# PowerSupp.net
KiCad netlist of a schematic drawn in EAGLE
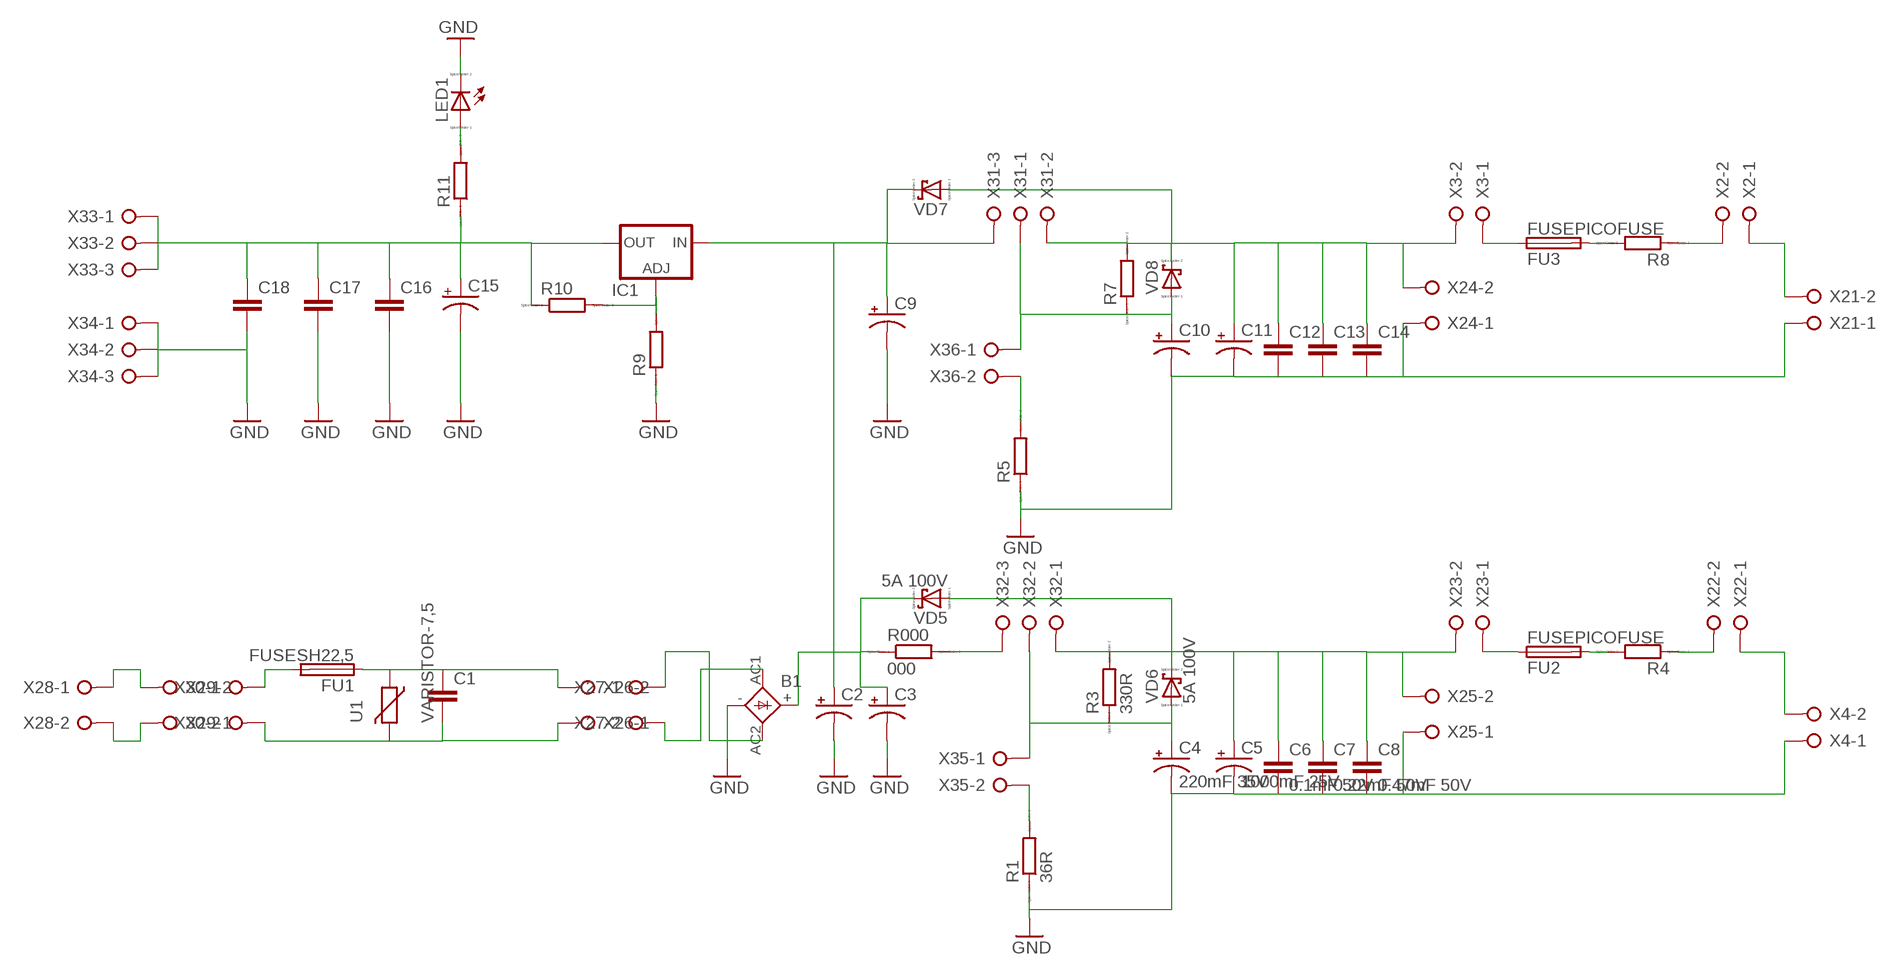
[diagram p0: schematic, sheet 1]

(export (version "E")
  (design (tool "Eeschema 10.0.6"))
  (components
    (comp (ref "B1")
      (value "KBU")
      (footprint "eagle-import:KBU")
      (libsource (lib "eagle-import") (part "KBU"))
    )
    (comp (ref "C1")
      (value "C15/8")
      (footprint "eagle-import:C15B8")
      (libsource (lib "eagle-import") (part "C15/8"))
    )
    (comp (ref "C2")
      (value "CPOL-USE7.5-16")
      (footprint "eagle-import:E7,5-16")
      (libsource (lib "eagle-import") (part "CPOL-USE7.5-16"))
    )
    (comp (ref "C3")
      (value "CPOL-USE7.5-16")
      (footprint "eagle-import:E7,5-16")
      (libsource (lib "eagle-import") (part "CPOL-USE7.5-16"))
    )
    (comp (ref "C4")
      (value "220mF 35V")
      (footprint "eagle-import:E5-10,5")
      (libsource (lib "eagle-import") (part "CPOL-USE5-10.5"))
    )
    (comp (ref "C5")
      (value "1000mF 25V")
      (footprint "eagle-import:E5-13")
      (libsource (lib "eagle-import") (part "CPOL-USE5-13"))
    )
    (comp (ref "C6")
      (value "0.1mF 50V")
      (footprint "eagle-import:C050-045X075")
      (libsource (lib "eagle-import") (part "C-EU050-045X075"))
    )
    (comp (ref "C7")
      (value "0.22mF 50V")
      (footprint "eagle-import:C050-045X075")
      (libsource (lib "eagle-import") (part "C-EU050-045X075"))
    )
    (comp (ref "C8")
      (value "0.47mF 50V")
      (footprint "eagle-import:C050-045X075")
      (libsource (lib "eagle-import") (part "C-EU050-045X075"))
    )
    (comp (ref "C9")
      (value "CPOL-USE7.5-16")
      (footprint "eagle-import:E7,5-16")
      (libsource (lib "eagle-import") (part "CPOL-USE7.5-16"))
    )
    (comp (ref "C10")
      (value "CPOL-USE5-10.5")
      (footprint "eagle-import:E5-10,5")
      (libsource (lib "eagle-import") (part "CPOL-USE5-10.5"))
    )
    (comp (ref "C11")
      (value "CPOL-USE5-13")
      (footprint "eagle-import:E5-13")
      (libsource (lib "eagle-import") (part "CPOL-USE5-13"))
    )
    (comp (ref "C12")
      (value "C-EU050-045X075")
      (footprint "eagle-import:C050-045X075")
      (libsource (lib "eagle-import") (part "C-EU050-045X075"))
    )
    (comp (ref "C13")
      (value "C-EU050-045X075")
      (footprint "eagle-import:C050-045X075")
      (libsource (lib "eagle-import") (part "C-EU050-045X075"))
    )
    (comp (ref "C14")
      (value "C-EU050-045X075")
      (footprint "eagle-import:C050-045X075")
      (libsource (lib "eagle-import") (part "C-EU050-045X075"))
    )
    (comp (ref "C15")
      (value "CPOL-USE5-10.5")
      (footprint "eagle-import:E5-10,5")
      (libsource (lib "eagle-import") (part "CPOL-USE5-10.5"))
    )
    (comp (ref "C16")
      (value "C-EU050-045X075")
      (footprint "eagle-import:C050-045X075")
      (libsource (lib "eagle-import") (part "C-EU050-045X075"))
    )
    (comp (ref "C17")
      (value "C-EU050-045X075")
      (footprint "eagle-import:C050-045X075")
      (libsource (lib "eagle-import") (part "C-EU050-045X075"))
    )
    (comp (ref "C18")
      (value "C-EU050-045X075")
      (footprint "eagle-import:C050-045X075")
      (libsource (lib "eagle-import") (part "C-EU050-045X075"))
    )
    (comp (ref "FU1")
      (value "FUSESH22,5")
      (footprint "eagle-import:SH22,5")
      (libsource (lib "eagle-import") (part "FUSESH22,5"))
    )
    (comp (ref "FU2")
      (value "FUSEPICOFUSE")
      (footprint "eagle-import:PICOFUSE")
      (libsource (lib "eagle-import") (part "FUSEPICOFUSE"))
    )
    (comp (ref "FU3")
      (value "FUSEPICOFUSE")
      (footprint "eagle-import:PICOFUSE")
      (libsource (lib "eagle-import") (part "FUSEPICOFUSE"))
    )
    (comp (ref "IC1")
      (value "LM317TL")
      (footprint "eagle-import:317TL")
      (libsource (lib "eagle-import") (part "LM317TL"))
    )
    (comp (ref "LED1")
      (value "LED_ELD260")
      (footprint "eagle-import:LED_LD260")
      (libsource (lib "eagle-import") (part "LED_ELD260"))
    )
    (comp (ref "R000")
      (value "000")
      (footprint "eagle-import:0207_10")
      (libsource (lib "eagle-import") (part "R0207/10"))
    )
    (comp (ref "R1")
      (value "36R")
      (footprint "eagle-import:0207_10")
      (libsource (lib "eagle-import") (part "R0207/10"))
    )
    (comp (ref "R3")
      (value "330R")
      (footprint "eagle-import:0207_10")
      (libsource (lib "eagle-import") (part "R0207/10"))
    )
    (comp (ref "R4")
      (value "R0207/10")
      (footprint "eagle-import:0207_10")
      (libsource (lib "eagle-import") (part "R0207/10"))
    )
    (comp (ref "R5")
      (value "R0207/10")
      (footprint "eagle-import:0207_10")
      (libsource (lib "eagle-import") (part "R0207/10"))
    )
    (comp (ref "R7")
      (value "R0207/10")
      (footprint "eagle-import:0207_10")
      (libsource (lib "eagle-import") (part "R0207/10"))
    )
    (comp (ref "R8")
      (value "R0207/10")
      (footprint "eagle-import:0207_10")
      (libsource (lib "eagle-import") (part "R0207/10"))
    )
    (comp (ref "R9")
      (value "R0207/10")
      (footprint "eagle-import:0207_10")
      (libsource (lib "eagle-import") (part "R0207/10"))
    )
    (comp (ref "R10")
      (value "R0207/10")
      (footprint "eagle-import:0207_10")
      (libsource (lib "eagle-import") (part "R0207/10"))
    )
    (comp (ref "R11")
      (value "R0207/10")
      (footprint "eagle-import:0207_10")
      (libsource (lib "eagle-import") (part "R0207/10"))
    )
    (comp (ref "U1")
      (value "VARISTOR-7,5")
      (footprint "eagle-import:R-7,5")
      (libsource (lib "eagle-import") (part "VARISTOR-7,5"))
    )
    (comp (ref "VD5")
      (value "5A 100V")
      (footprint "eagle-import:DIODE_F126Z12")
      (libsource (lib "eagle-import") (part "SCHOTTKY-DIODEF126Z12"))
    )
    (comp (ref "VD6")
      (value "5A 100V")
      (footprint "eagle-import:DIODE_F126Z12")
      (libsource (lib "eagle-import") (part "SCHOTTKY-DIODEF126Z12"))
    )
    (comp (ref "VD7")
      (value "SCHOTTKY-DIODEF126Z12")
      (footprint "eagle-import:DIODE_F126Z12")
      (libsource (lib "eagle-import") (part "SCHOTTKY-DIODEF126Z12"))
    )
    (comp (ref "VD8")
      (value "SCHOTTKY-DIODEF126Z12")
      (footprint "eagle-import:DIODE_F126Z12")
      (libsource (lib "eagle-import") (part "SCHOTTKY-DIODEF126Z12"))
    )
    (comp (ref "X2")
      (value "W237-02P")
      (footprint "eagle-import:W237-132")
      (libsource (lib "eagle-import") (part "W237-02P"))
    )
    (comp (ref "X3")
      (value "W237-02P")
      (footprint "eagle-import:W237-132")
      (libsource (lib "eagle-import") (part "W237-02P"))
    )
    (comp (ref "X4")
      (value "W237-02P")
      (footprint "eagle-import:W237-132")
      (libsource (lib "eagle-import") (part "W237-02P"))
    )
    (comp (ref "X21")
      (value "W237-02P")
      (footprint "eagle-import:W237-132")
      (libsource (lib "eagle-import") (part "W237-02P"))
    )
    (comp (ref "X22")
      (value "W237-02P")
      (footprint "eagle-import:W237-132")
      (libsource (lib "eagle-import") (part "W237-02P"))
    )
    (comp (ref "X23")
      (value "W237-02P")
      (footprint "eagle-import:W237-132")
      (libsource (lib "eagle-import") (part "W237-02P"))
    )
    (comp (ref "X24")
      (value "W237-02P")
      (footprint "eagle-import:W237-132")
      (libsource (lib "eagle-import") (part "W237-02P"))
    )
    (comp (ref "X25")
      (value "W237-02P")
      (footprint "eagle-import:W237-132")
      (libsource (lib "eagle-import") (part "W237-02P"))
    )
    (comp (ref "X26")
      (value "W237-02P")
      (footprint "eagle-import:W237-132")
      (libsource (lib "eagle-import") (part "W237-02P"))
    )
    (comp (ref "X27")
      (value "W237-02P")
      (footprint "eagle-import:W237-132")
      (libsource (lib "eagle-import") (part "W237-02P"))
    )
    (comp (ref "X28")
      (value "W237-02P")
      (footprint "eagle-import:W237-132")
      (libsource (lib "eagle-import") (part "W237-02P"))
    )
    (comp (ref "X29")
      (value "W237-02P")
      (footprint "eagle-import:W237-132")
      (libsource (lib "eagle-import") (part "W237-02P"))
    )
    (comp (ref "X30")
      (value "W237-02P")
      (footprint "eagle-import:W237-132")
      (libsource (lib "eagle-import") (part "W237-02P"))
    )
    (comp (ref "X31")
      (value "W237-3E")
      (footprint "eagle-import:W237-3E")
      (libsource (lib "eagle-import") (part "W237-3E"))
    )
    (comp (ref "X32")
      (value "W237-3E")
      (footprint "eagle-import:W237-3E")
      (libsource (lib "eagle-import") (part "W237-3E"))
    )
    (comp (ref "X33")
      (value "W237-3E")
      (footprint "eagle-import:W237-3E")
      (libsource (lib "eagle-import") (part "W237-3E"))
    )
    (comp (ref "X34")
      (value "W237-3E")
      (footprint "eagle-import:W237-3E")
      (libsource (lib "eagle-import") (part "W237-3E"))
    )
    (comp (ref "X35")
      (value "W237-02P")
      (footprint "eagle-import:W237-132")
      (libsource (lib "eagle-import") (part "W237-02P"))
    )
    (comp (ref "X36")
      (value "W237-02P")
      (footprint "eagle-import:W237-132")
      (libsource (lib "eagle-import") (part "W237-02P"))
    )
  )
  (nets
    (net (code "1") (name "GND") (class "Default")
      (node (ref "B1") (pin "-") (pinfunction "-_-") (pintype "passive"))
      (node (ref "C10") (pin "-") (pinfunction "-_-") (pintype "passive"))
      (node (ref "C11") (pin "-") (pinfunction "-_-") (pintype "passive"))
      (node (ref "C12") (pin "2") (pinfunction "2_2") (pintype "passive"))
      (node (ref "C13") (pin "2") (pinfunction "2_2") (pintype "passive"))
      (node (ref "C14") (pin "2") (pinfunction "2_2") (pintype "passive"))
      (node (ref "C15") (pin "-") (pinfunction "-_-") (pintype "passive"))
      (node (ref "C16") (pin "2") (pinfunction "2_2") (pintype "passive"))
      (node (ref "C17") (pin "2") (pinfunction "2_2") (pintype "passive"))
      (node (ref "C18") (pin "2") (pinfunction "2_2") (pintype "passive"))
      (node (ref "C2") (pin "-") (pinfunction "-_-") (pintype "passive"))
      (node (ref "C3") (pin "-") (pinfunction "-_-") (pintype "passive"))
      (node (ref "C4") (pin "-") (pinfunction "-_-") (pintype "passive"))
      (node (ref "C5") (pin "-") (pinfunction "-_-") (pintype "passive"))
      (node (ref "C6") (pin "2") (pinfunction "2_2") (pintype "passive"))
      (node (ref "C7") (pin "2") (pinfunction "2_2") (pintype "passive"))
      (node (ref "C8") (pin "2") (pinfunction "2_2") (pintype "passive"))
      (node (ref "C9") (pin "-") (pinfunction "-_-") (pintype "passive"))
      (node (ref "LED1") (pin "K") (pinfunction "C_K") (pintype "passive"))
      (node (ref "R1") (pin "1") (pinfunction "1_1") (pintype "passive"))
      (node (ref "R5") (pin "1") (pinfunction "1_1") (pintype "passive"))
      (node (ref "R9") (pin "1") (pinfunction "1_1") (pintype "passive"))
      (node (ref "X21") (pin "1") (pinfunction "KL_1") (pintype "passive"))
      (node (ref "X24") (pin "1") (pinfunction "KL_1") (pintype "passive"))
      (node (ref "X25") (pin "1") (pinfunction "KL_1") (pintype "passive"))
      (node (ref "X34") (pin "1") (pinfunction "KL_1") (pintype "passive"))
      (node (ref "X34") (pin "2") (pinfunction "KL_2") (pintype "passive"))
      (node (ref "X34") (pin "3") (pinfunction "KL_3") (pintype "passive"))
      (node (ref "X4") (pin "1") (pinfunction "KL_1") (pintype "passive"))
    )
    (net (code "2") (name "Net-(FU2-Pad2)") (class "Default")
      (node (ref "FU2") (pin "2") (pinfunction "2_2") (pintype "passive"))
      (node (ref "R4") (pin "2") (pinfunction "2_2") (pintype "passive"))
    )
    (net (code "3") (name "Net-(FU3-Pad2)") (class "Default")
      (node (ref "FU3") (pin "2") (pinfunction "2_2") (pintype "passive"))
      (node (ref "R8") (pin "2") (pinfunction "2_2") (pintype "passive"))
    )
    (net (code "4") (name "Net-(IC1-ADJ)") (class "Default")
      (node (ref "IC1") (pin "1") (pinfunction "ADJ_1") (pintype "input"))
      (node (ref "R10") (pin "2") (pinfunction "2_2") (pintype "passive"))
      (node (ref "R9") (pin "2") (pinfunction "2_2") (pintype "passive"))
    )
    (net (code "5") (name "Net-(IC1-IN)") (class "Default")
      (node (ref "B1") (pin "+") (pinfunction "+_+") (pintype "passive"))
      (node (ref "C2") (pin "+") (pinfunction "+_+") (pintype "passive"))
      (node (ref "C3") (pin "+") (pinfunction "+_+") (pintype "passive"))
      (node (ref "C9") (pin "+") (pinfunction "+_+") (pintype "passive"))
      (node (ref "IC1") (pin "3") (pinfunction "IN_3") (pintype "input"))
      (node (ref "R000") (pin "1") (pinfunction "1_1") (pintype "passive"))
      (node (ref "VD5") (pin "C") (pinfunction "A_C") (pintype "passive"))
      (node (ref "VD7") (pin "C") (pinfunction "A_C") (pintype "passive"))
      (node (ref "X31") (pin "3") (pinfunction "KL_3") (pintype "passive"))
    )
    (net (code "6") (name "Net-(IC1-OUT)") (class "Default")
      (node (ref "C15") (pin "+") (pinfunction "+_+") (pintype "passive"))
      (node (ref "C16") (pin "1") (pinfunction "1_1") (pintype "passive"))
      (node (ref "C17") (pin "1") (pinfunction "1_1") (pintype "passive"))
      (node (ref "C18") (pin "1") (pinfunction "1_1") (pintype "passive"))
      (node (ref "IC1") (pin "2") (pinfunction "OUT_2") (pintype "passive"))
      (node (ref "R10") (pin "1") (pinfunction "1_1") (pintype "passive"))
      (node (ref "R11") (pin "1") (pinfunction "1_1") (pintype "passive"))
      (node (ref "X33") (pin "1") (pinfunction "KL_1") (pintype "passive"))
      (node (ref "X33") (pin "2") (pinfunction "KL_2") (pintype "passive"))
      (node (ref "X33") (pin "3") (pinfunction "KL_3") (pintype "passive"))
    )
    (net (code "7") (name "Net-(LED1-PadA)") (class "Default")
      (node (ref "LED1") (pin "A") (pinfunction "A_A") (pintype "passive"))
      (node (ref "R11") (pin "2") (pinfunction "2_2") (pintype "passive"))
    )
    (net (code "8") (name "Net-(VD5-C)") (class "Default")
      (node (ref "C5") (pin "+") (pinfunction "+_+") (pintype "passive"))
      (node (ref "C6") (pin "1") (pinfunction "1_1") (pintype "passive"))
      (node (ref "C7") (pin "1") (pinfunction "1_1") (pintype "passive"))
      (node (ref "C8") (pin "1") (pinfunction "1_1") (pintype "passive"))
      (node (ref "R3") (pin "2") (pinfunction "2_2") (pintype "passive"))
      (node (ref "VD5") (pin "A") (pinfunction "C_A") (pintype "passive"))
      (node (ref "VD6") (pin "C") (pinfunction "A_C") (pintype "passive"))
      (node (ref "X23") (pin "2") (pinfunction "KL_2") (pintype "passive"))
      (node (ref "X25") (pin "2") (pinfunction "KL_2") (pintype "passive"))
      (node (ref "X32") (pin "1") (pinfunction "KL_1") (pintype "passive"))
    )
    (net (code "9") (name "Net-(VD6-C)") (class "Default")
      (node (ref "C4") (pin "+") (pinfunction "+_+") (pintype "passive"))
      (node (ref "R3") (pin "1") (pinfunction "1_1") (pintype "passive"))
      (node (ref "VD6") (pin "A") (pinfunction "C_A") (pintype "passive"))
      (node (ref "X32") (pin "2") (pinfunction "KL_2") (pintype "passive"))
      (node (ref "X35") (pin "1") (pinfunction "KL_1") (pintype "passive"))
    )
    (net (code "10") (name "Net-(VD7-C)") (class "Default")
      (node (ref "C11") (pin "+") (pinfunction "+_+") (pintype "passive"))
      (node (ref "C12") (pin "1") (pinfunction "1_1") (pintype "passive"))
      (node (ref "C13") (pin "1") (pinfunction "1_1") (pintype "passive"))
      (node (ref "C14") (pin "1") (pinfunction "1_1") (pintype "passive"))
      (node (ref "R7") (pin "2") (pinfunction "2_2") (pintype "passive"))
      (node (ref "VD7") (pin "A") (pinfunction "C_A") (pintype "passive"))
      (node (ref "VD8") (pin "C") (pinfunction "A_C") (pintype "passive"))
      (node (ref "X24") (pin "2") (pinfunction "KL_2") (pintype "passive"))
      (node (ref "X3") (pin "2") (pinfunction "KL_2") (pintype "passive"))
      (node (ref "X31") (pin "2") (pinfunction "KL_2") (pintype "passive"))
    )
    (net (code "11") (name "Net-(VD8-C)") (class "Default")
      (node (ref "C10") (pin "+") (pinfunction "+_+") (pintype "passive"))
      (node (ref "R7") (pin "1") (pinfunction "1_1") (pintype "passive"))
      (node (ref "VD8") (pin "A") (pinfunction "C_A") (pintype "passive"))
      (node (ref "X31") (pin "1") (pinfunction "KL_1") (pintype "passive"))
      (node (ref "X36") (pin "1") (pinfunction "KL_1") (pintype "passive"))
    )
    (net (code "12") (name "Net-(X2B-KL)") (class "Default")
      (node (ref "R8") (pin "1") (pinfunction "1_1") (pintype "passive"))
      (node (ref "X2") (pin "2") (pinfunction "KL_2") (pintype "passive"))
    )
    (net (code "13") (name "Net-(X3A-KL)") (class "Default")
      (node (ref "FU3") (pin "1") (pinfunction "1_1") (pintype "passive"))
      (node (ref "X3") (pin "1") (pinfunction "KL_1") (pintype "passive"))
    )
    (net (code "14") (name "Net-(X21B-KL)") (class "Default")
      (node (ref "X2") (pin "1") (pinfunction "KL_1") (pintype "passive"))
      (node (ref "X21") (pin "2") (pinfunction "KL_2") (pintype "passive"))
    )
    (net (code "15") (name "Net-(X22A-KL)") (class "Default")
      (node (ref "X22") (pin "1") (pinfunction "KL_1") (pintype "passive"))
      (node (ref "X4") (pin "2") (pinfunction "KL_2") (pintype "passive"))
    )
    (net (code "16") (name "Net-(X22B-KL)") (class "Default")
      (node (ref "R4") (pin "1") (pinfunction "1_1") (pintype "passive"))
      (node (ref "X22") (pin "2") (pinfunction "KL_2") (pintype "passive"))
    )
    (net (code "17") (name "Net-(X23A-KL)") (class "Default")
      (node (ref "FU2") (pin "1") (pinfunction "1_1") (pintype "passive"))
      (node (ref "X23") (pin "1") (pinfunction "KL_1") (pintype "passive"))
    )
    (net (code "18") (name "Net-(X26A-KL)") (class "Default")
      (node (ref "C1") (pin "2") (pinfunction "2_2") (pintype "passive"))
      (node (ref "U1") (pin "2") (pinfunction "2_2") (pintype "passive"))
      (node (ref "X26") (pin "1") (pinfunction "KL_1") (pintype "passive"))
      (node (ref "X30") (pin "2") (pinfunction "KL_2") (pintype "passive"))
    )
    (net (code "19") (name "Net-(X26B-KL)") (class "Default")
      (node (ref "C1") (pin "1") (pinfunction "1_1") (pintype "passive"))
      (node (ref "FU1") (pin "1") (pinfunction "1_1") (pintype "passive"))
      (node (ref "U1") (pin "1") (pinfunction "1_1") (pintype "passive"))
      (node (ref "X26") (pin "2") (pinfunction "KL_2") (pintype "passive"))
    )
    (net (code "20") (name "Net-(X27A-KL)") (class "Default")
      (node (ref "B1") (pin "AC2") (pinfunction "AC2_AC2") (pintype "passive"))
      (node (ref "X27") (pin "1") (pinfunction "KL_1") (pintype "passive"))
    )
    (net (code "21") (name "Net-(X27B-KL)") (class "Default")
      (node (ref "B1") (pin "AC1") (pinfunction "AC1_AC1") (pintype "passive"))
      (node (ref "X27") (pin "2") (pinfunction "KL_2") (pintype "passive"))
    )
    (net (code "22") (name "Net-(X28A-KL)") (class "Default")
      (node (ref "X28") (pin "1") (pinfunction "KL_1") (pintype "passive"))
      (node (ref "X29") (pin "2") (pinfunction "KL_2") (pintype "passive"))
    )
    (net (code "23") (name "Net-(X28B-KL)") (class "Default")
      (node (ref "X28") (pin "2") (pinfunction "KL_2") (pintype "passive"))
      (node (ref "X29") (pin "1") (pinfunction "KL_1") (pintype "passive"))
    )
    (net (code "24") (name "Net-(X30A-KL)") (class "Default")
      (node (ref "FU1") (pin "2") (pinfunction "2_2") (pintype "passive"))
      (node (ref "X30") (pin "1") (pinfunction "KL_1") (pintype "passive"))
    )
    (net (code "25") (name "Net-(X32C-KL)") (class "Default")
      (node (ref "R000") (pin "2") (pinfunction "2_2") (pintype "passive"))
      (node (ref "X32") (pin "3") (pinfunction "KL_3") (pintype "passive"))
    )
    (net (code "26") (name "Net-(X35B-KL)") (class "Default")
      (node (ref "R1") (pin "2") (pinfunction "2_2") (pintype "passive"))
      (node (ref "X35") (pin "2") (pinfunction "KL_2") (pintype "passive"))
    )
    (net (code "27") (name "Net-(X36B-KL)") (class "Default")
      (node (ref "R5") (pin "2") (pinfunction "2_2") (pintype "passive"))
      (node (ref "X36") (pin "2") (pinfunction "KL_2") (pintype "passive"))
    )
  )
)
